# Connectors_2.net
KiCad netlist of a schematic drawn in Altium Designer
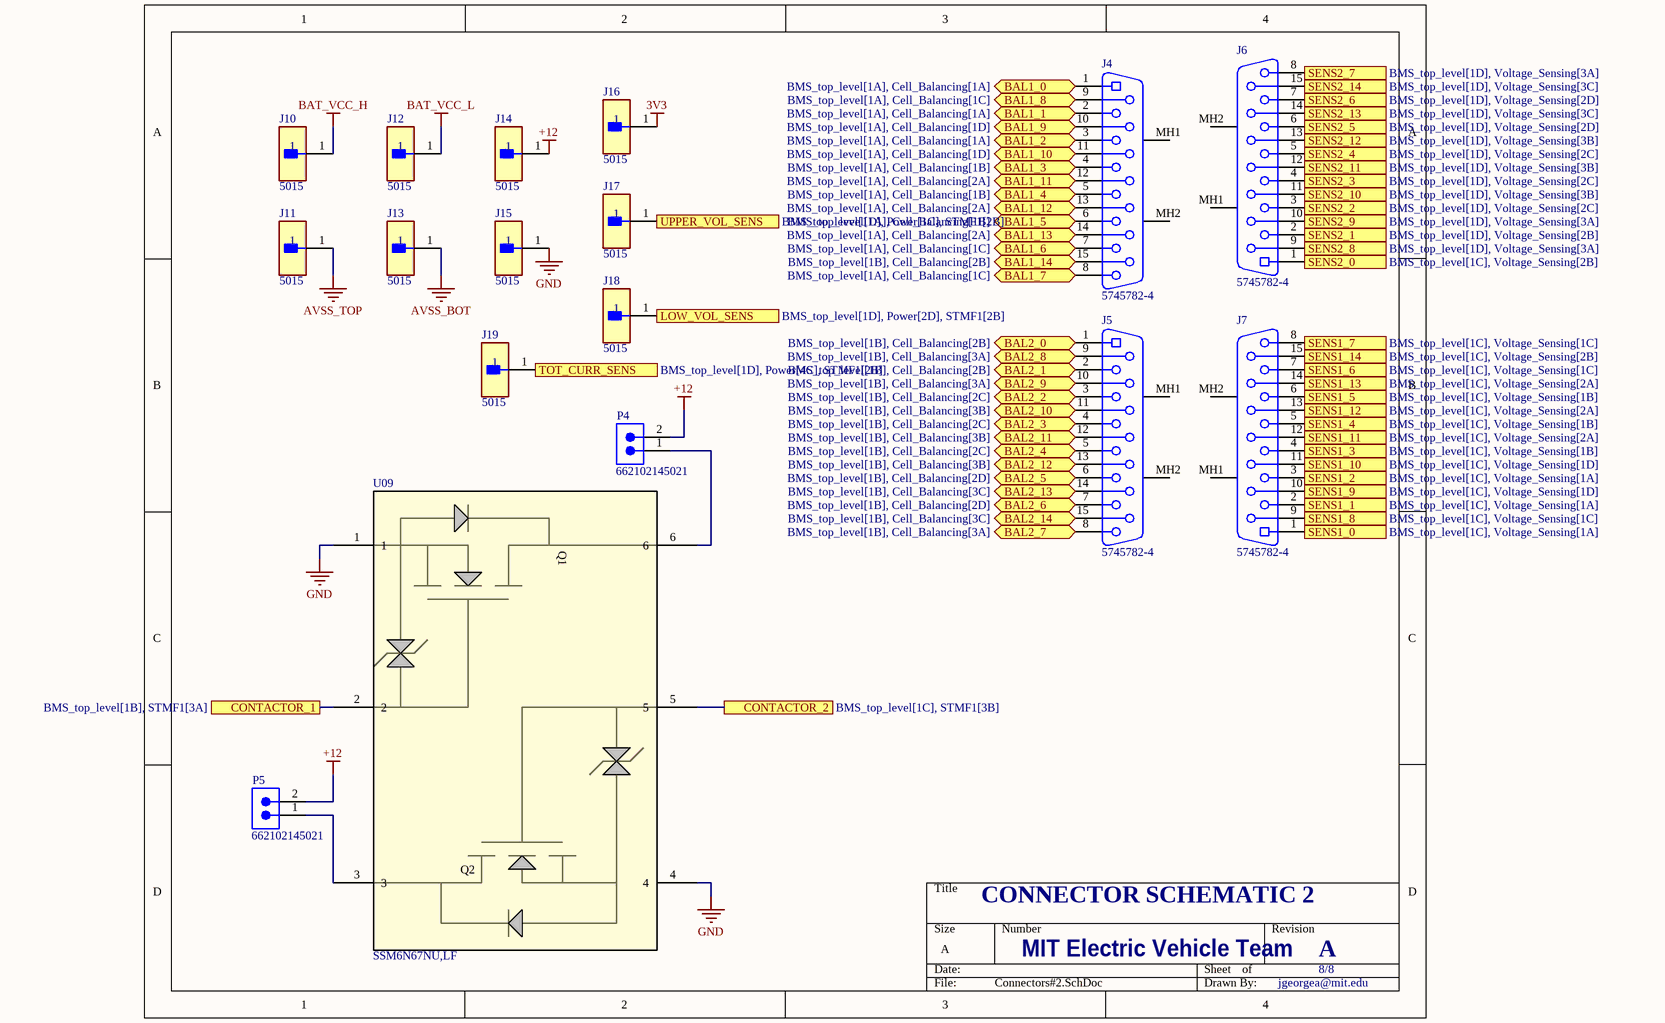
[diagram p0: Connectors#2.SchDoc]

(export (version "E")
  (design (tool "Eeschema 10.0.6"))
  (components
    (comp (ref "J4")
      (value "5745782-4")
      (footprint "TECO-5745782-4_V")
      (fields (field (name "MANUFACTURER") "TE Connectivity"))
      (libsource (lib "") (part "CN-2S-2F-D15_1"))
    )
    (comp (ref "J5")
      (value "5745782-4")
      (footprint "TECO-5745782-4_V")
      (fields (field (name "MANUFACTURER") "TE Connectivity"))
      (libsource (lib "") (part "CN-2S-2F-D15_1"))
    )
    (comp (ref "J6")
      (value "5745782-4")
      (footprint "TECO-5745782-4_V")
      (fields (field (name "MANUFACTURER") "TE Connectivity"))
      (libsource (lib "Altium Content Vault") (part "CN-2S-2F-D15"))
    )
    (comp (ref "J7")
      (value "5745782-4")
      (footprint "TECO-5745782-4_V")
      (fields (field (name "MANUFACTURER") "TE Connectivity"))
      (libsource (lib "Altium Content Vault") (part "CN-2S-2F-D15"))
    )
    (comp (ref "J10")
      (value "5015")
      (footprint "FP-5015-MFG")
      (description "PC TEST POINT MINIATURE")
      (fields
        (field (name "MANUFACTURER") "keystone")
        (field (name "OCTOPART") "https://octopart.com/5015-keystone-3822")
      )
      (libsource (lib "Altium Content Vault") (part "dd45045ce8184df9e99e12baf3f412c"))
    )
    (comp (ref "J11")
      (value "5015")
      (footprint "FP-5015-MFG")
      (description "PC TEST POINT MINIATURE")
      (fields
        (field (name "MANUFACTURER") "keystone")
        (field (name "OCTOPART") "https://octopart.com/5015-keystone-3822")
      )
      (libsource (lib "Altium Content Vault") (part "dd45045ce8184df9e99e12baf3f412c"))
    )
    (comp (ref "J12")
      (value "5015")
      (footprint "FP-5015-MFG")
      (description "PC TEST POINT MINIATURE")
      (fields
        (field (name "MANUFACTURER") "keystone")
        (field (name "OCTOPART") "https://octopart.com/5015-keystone-3822")
      )
      (libsource (lib "Altium Content Vault") (part "dd45045ce8184df9e99e12baf3f412c"))
    )
    (comp (ref "J13")
      (value "5015")
      (footprint "FP-5015-MFG")
      (description "PC TEST POINT MINIATURE")
      (fields
        (field (name "MANUFACTURER") "keystone")
        (field (name "OCTOPART") "https://octopart.com/5015-keystone-3822")
      )
      (libsource (lib "Altium Content Vault") (part "dd45045ce8184df9e99e12baf3f412c"))
    )
    (comp (ref "J14")
      (value "5015")
      (footprint "FP-5015-MFG")
      (description "PC TEST POINT MINIATURE")
      (fields
        (field (name "MANUFACTURER") "keystone")
        (field (name "OCTOPART") "https://octopart.com/5015-keystone-3822")
      )
      (libsource (lib "Altium Content Vault") (part "dd45045ce8184df9e99e12baf3f412c"))
    )
    (comp (ref "J15")
      (value "5015")
      (footprint "FP-5015-MFG")
      (description "PC TEST POINT MINIATURE")
      (fields
        (field (name "MANUFACTURER") "keystone")
        (field (name "OCTOPART") "https://octopart.com/5015-keystone-3822")
      )
      (libsource (lib "Altium Content Vault") (part "dd45045ce8184df9e99e12baf3f412c"))
    )
    (comp (ref "J16")
      (value "5015")
      (footprint "FP-5015-MFG")
      (description "PC TEST POINT MINIATURE")
      (fields
        (field (name "MANUFACTURER") "keystone")
        (field (name "OCTOPART") "https://octopart.com/5015-keystone-3822")
      )
      (libsource (lib "Altium Content Vault") (part "dd45045ce8184df9e99e12baf3f412c"))
    )
    (comp (ref "J17")
      (value "5015")
      (footprint "FP-5015-MFG")
      (description "PC TEST POINT MINIATURE")
      (fields
        (field (name "MANUFACTURER") "keystone")
        (field (name "OCTOPART") "https://octopart.com/5015-keystone-3822")
      )
      (libsource (lib "Altium Content Vault") (part "dd45045ce8184df9e99e12baf3f412c"))
    )
    (comp (ref "J18")
      (value "5015")
      (footprint "FP-5015-MFG")
      (description "PC TEST POINT MINIATURE")
      (fields
        (field (name "MANUFACTURER") "keystone")
        (field (name "OCTOPART") "https://octopart.com/5015-keystone-3822")
      )
      (libsource (lib "Altium Content Vault") (part "dd45045ce8184df9e99e12baf3f412c"))
    )
    (comp (ref "J19")
      (value "5015")
      (footprint "FP-5015-MFG")
      (description "PC TEST POINT MINIATURE")
      (fields
        (field (name "MANUFACTURER") "keystone")
        (field (name "OCTOPART") "https://octopart.com/5015-keystone-3822")
      )
      (libsource (lib "Altium Content Vault") (part "dd45045ce8184df9e99e12baf3f412c"))
    )
    (comp (ref "P4")
      (value "662102145021")
      (footprint "662102145021")
      (libsource (lib "Altium Content Vault") (part "Header_Male_1R_02P"))
    )
    (comp (ref "P5")
      (value "662102145021")
      (footprint "662102145021")
      (libsource (lib "Altium Content Vault") (part "Header_Male_1R_02P"))
    )
    (comp (ref "U09")
      (value "SSM6N67NU,LF")
      (footprint "UDFN6_TOS")
      (description "No Description Available")
      (libsource (lib "SSM6N67NU,LF") (part "SSM6N67NU,LF"))
    )
  )
  (nets
    (net (code "1") (name "+12") (class "Default")
      (node (ref "J14") (pin "1") (pinfunction "1_1") (pintype "passive"))
      (node (ref "P4") (pin "2") (pinfunction "2_2") (pintype "passive"))
      (node (ref "P5") (pin "2") (pinfunction "2_2") (pintype "passive"))
    )
    (net (code "2") (name "/BAL1_0") (class "Default")
      (node (ref "J4") (pin "1") (pinfunction "1_1") (pintype "passive"))
    )
    (net (code "3") (name "/BAL1_1") (class "Default")
      (node (ref "J4") (pin "2") (pinfunction "2_2") (pintype "passive"))
    )
    (net (code "4") (name "/BAL1_2") (class "Default")
      (node (ref "J4") (pin "3") (pinfunction "3_3") (pintype "passive"))
    )
    (net (code "5") (name "/BAL1_3") (class "Default")
      (node (ref "J4") (pin "4") (pinfunction "4_4") (pintype "passive"))
    )
    (net (code "6") (name "/BAL1_4") (class "Default")
      (node (ref "J4") (pin "5") (pinfunction "5_5") (pintype "passive"))
    )
    (net (code "7") (name "/BAL1_5") (class "Default")
      (node (ref "J4") (pin "6") (pinfunction "6_6") (pintype "passive"))
    )
    (net (code "8") (name "/BAL1_6") (class "Default")
      (node (ref "J4") (pin "7") (pinfunction "7_7") (pintype "passive"))
    )
    (net (code "9") (name "/BAL1_7") (class "Default")
      (node (ref "J4") (pin "8") (pinfunction "8_8") (pintype "passive"))
    )
    (net (code "10") (name "/BAL1_8") (class "Default")
      (node (ref "J4") (pin "9") (pinfunction "9_9") (pintype "passive"))
    )
    (net (code "11") (name "/BAL1_9") (class "Default")
      (node (ref "J4") (pin "10") (pinfunction "10_10") (pintype "passive"))
    )
    (net (code "12") (name "/BAL1_10") (class "Default")
      (node (ref "J4") (pin "11") (pinfunction "11_11") (pintype "passive"))
    )
    (net (code "13") (name "/BAL1_11") (class "Default")
      (node (ref "J4") (pin "12") (pinfunction "12_12") (pintype "passive"))
    )
    (net (code "14") (name "/BAL1_12") (class "Default")
      (node (ref "J4") (pin "13") (pinfunction "13_13") (pintype "passive"))
    )
    (net (code "15") (name "/BAL1_13") (class "Default")
      (node (ref "J4") (pin "14") (pinfunction "14_14") (pintype "passive"))
    )
    (net (code "16") (name "/BAL1_14") (class "Default")
      (node (ref "J4") (pin "15") (pinfunction "15_15") (pintype "passive"))
    )
    (net (code "17") (name "/BAL2_0") (class "Default")
      (node (ref "J5") (pin "1") (pinfunction "1_1") (pintype "passive"))
    )
    (net (code "18") (name "/BAL2_1") (class "Default")
      (node (ref "J5") (pin "2") (pinfunction "2_2") (pintype "passive"))
    )
    (net (code "19") (name "/BAL2_2") (class "Default")
      (node (ref "J5") (pin "3") (pinfunction "3_3") (pintype "passive"))
    )
    (net (code "20") (name "/BAL2_3") (class "Default")
      (node (ref "J5") (pin "4") (pinfunction "4_4") (pintype "passive"))
    )
    (net (code "21") (name "/BAL2_4") (class "Default")
      (node (ref "J5") (pin "5") (pinfunction "5_5") (pintype "passive"))
    )
    (net (code "22") (name "/BAL2_5") (class "Default")
      (node (ref "J5") (pin "6") (pinfunction "6_6") (pintype "passive"))
    )
    (net (code "23") (name "/BAL2_6") (class "Default")
      (node (ref "J5") (pin "7") (pinfunction "7_7") (pintype "passive"))
    )
    (net (code "24") (name "/BAL2_7") (class "Default")
      (node (ref "J5") (pin "8") (pinfunction "8_8") (pintype "passive"))
    )
    (net (code "25") (name "/BAL2_8") (class "Default")
      (node (ref "J5") (pin "9") (pinfunction "9_9") (pintype "passive"))
    )
    (net (code "26") (name "/BAL2_9") (class "Default")
      (node (ref "J5") (pin "10") (pinfunction "10_10") (pintype "passive"))
    )
    (net (code "27") (name "/BAL2_10") (class "Default")
      (node (ref "J5") (pin "11") (pinfunction "11_11") (pintype "passive"))
    )
    (net (code "28") (name "/BAL2_11") (class "Default")
      (node (ref "J5") (pin "12") (pinfunction "12_12") (pintype "passive"))
    )
    (net (code "29") (name "/BAL2_12") (class "Default")
      (node (ref "J5") (pin "13") (pinfunction "13_13") (pintype "passive"))
    )
    (net (code "30") (name "/BAL2_13") (class "Default")
      (node (ref "J5") (pin "14") (pinfunction "14_14") (pintype "passive"))
    )
    (net (code "31") (name "/BAL2_14") (class "Default")
      (node (ref "J5") (pin "15") (pinfunction "15_15") (pintype "passive"))
    )
    (net (code "32") (name "/CONTACTOR_1") (class "Default")
      (node (ref "U09") (pin "2") (pinfunction "2_2") (pintype "passive"))
    )
    (net (code "33") (name "/CONTACTOR_2") (class "Default")
      (node (ref "U09") (pin "5") (pinfunction "5_5") (pintype "passive"))
    )
    (net (code "34") (name "/LOW_VOL_SENS") (class "Default")
      (node (ref "J18") (pin "1") (pinfunction "1_1") (pintype "passive"))
    )
    (net (code "35") (name "/SENS1_0") (class "Default")
      (node (ref "J7") (pin "1") (pinfunction "1_1") (pintype "passive"))
    )
    (net (code "36") (name "/SENS1_1") (class "Default")
      (node (ref "J7") (pin "2") (pinfunction "2_2") (pintype "passive"))
    )
    (net (code "37") (name "/SENS1_2") (class "Default")
      (node (ref "J7") (pin "3") (pinfunction "3_3") (pintype "passive"))
    )
    (net (code "38") (name "/SENS1_3") (class "Default")
      (node (ref "J7") (pin "4") (pinfunction "4_4") (pintype "passive"))
    )
    (net (code "39") (name "/SENS1_4") (class "Default")
      (node (ref "J7") (pin "5") (pinfunction "5_5") (pintype "passive"))
    )
    (net (code "40") (name "/SENS1_5") (class "Default")
      (node (ref "J7") (pin "6") (pinfunction "6_6") (pintype "passive"))
    )
    (net (code "41") (name "/SENS1_6") (class "Default")
      (node (ref "J7") (pin "7") (pinfunction "7_7") (pintype "passive"))
    )
    (net (code "42") (name "/SENS1_7") (class "Default")
      (node (ref "J7") (pin "8") (pinfunction "8_8") (pintype "passive"))
    )
    (net (code "43") (name "/SENS1_8") (class "Default")
      (node (ref "J7") (pin "9") (pinfunction "9_9") (pintype "passive"))
    )
    (net (code "44") (name "/SENS1_9") (class "Default")
      (node (ref "J7") (pin "10") (pinfunction "10_10") (pintype "passive"))
    )
    (net (code "45") (name "/SENS1_10") (class "Default")
      (node (ref "J7") (pin "11") (pinfunction "11_11") (pintype "passive"))
    )
    (net (code "46") (name "/SENS1_11") (class "Default")
      (node (ref "J7") (pin "12") (pinfunction "12_12") (pintype "passive"))
    )
    (net (code "47") (name "/SENS1_12") (class "Default")
      (node (ref "J7") (pin "13") (pinfunction "13_13") (pintype "passive"))
    )
    (net (code "48") (name "/SENS1_13") (class "Default")
      (node (ref "J7") (pin "14") (pinfunction "14_14") (pintype "passive"))
    )
    (net (code "49") (name "/SENS1_14") (class "Default")
      (node (ref "J7") (pin "15") (pinfunction "15_15") (pintype "passive"))
    )
    (net (code "50") (name "/SENS2_0") (class "Default")
      (node (ref "J6") (pin "1") (pinfunction "1_1") (pintype "passive"))
    )
    (net (code "51") (name "/SENS2_1") (class "Default")
      (node (ref "J6") (pin "2") (pinfunction "2_2") (pintype "passive"))
    )
    (net (code "52") (name "/SENS2_2") (class "Default")
      (node (ref "J6") (pin "3") (pinfunction "3_3") (pintype "passive"))
    )
    (net (code "53") (name "/SENS2_3") (class "Default")
      (node (ref "J6") (pin "4") (pinfunction "4_4") (pintype "passive"))
    )
    (net (code "54") (name "/SENS2_4") (class "Default")
      (node (ref "J6") (pin "5") (pinfunction "5_5") (pintype "passive"))
    )
    (net (code "55") (name "/SENS2_5") (class "Default")
      (node (ref "J6") (pin "6") (pinfunction "6_6") (pintype "passive"))
    )
    (net (code "56") (name "/SENS2_6") (class "Default")
      (node (ref "J6") (pin "7") (pinfunction "7_7") (pintype "passive"))
    )
    (net (code "57") (name "/SENS2_7") (class "Default")
      (node (ref "J6") (pin "8") (pinfunction "8_8") (pintype "passive"))
    )
    (net (code "58") (name "/SENS2_8") (class "Default")
      (node (ref "J6") (pin "9") (pinfunction "9_9") (pintype "passive"))
    )
    (net (code "59") (name "/SENS2_9") (class "Default")
      (node (ref "J6") (pin "10") (pinfunction "10_10") (pintype "passive"))
    )
    (net (code "60") (name "/SENS2_10") (class "Default")
      (node (ref "J6") (pin "11") (pinfunction "11_11") (pintype "passive"))
    )
    (net (code "61") (name "/SENS2_11") (class "Default")
      (node (ref "J6") (pin "12") (pinfunction "12_12") (pintype "passive"))
    )
    (net (code "62") (name "/SENS2_12") (class "Default")
      (node (ref "J6") (pin "13") (pinfunction "13_13") (pintype "passive"))
    )
    (net (code "63") (name "/SENS2_13") (class "Default")
      (node (ref "J6") (pin "14") (pinfunction "14_14") (pintype "passive"))
    )
    (net (code "64") (name "/SENS2_14") (class "Default")
      (node (ref "J6") (pin "15") (pinfunction "15_15") (pintype "passive"))
    )
    (net (code "65") (name "/TOT_CURR_SENS") (class "Default")
      (node (ref "J19") (pin "1") (pinfunction "1_1") (pintype "passive"))
    )
    (net (code "66") (name "/UPPER_VOL_SENS") (class "Default")
      (node (ref "J17") (pin "1") (pinfunction "1_1") (pintype "passive"))
    )
    (net (code "67") (name "3V3") (class "Default")
      (node (ref "J16") (pin "1") (pinfunction "1_1") (pintype "passive"))
    )
    (net (code "68") (name "AVSS_BOT") (class "Default")
      (node (ref "J13") (pin "1") (pinfunction "1_1") (pintype "passive"))
    )
    (net (code "69") (name "AVSS_TOP") (class "Default")
      (node (ref "J11") (pin "1") (pinfunction "1_1") (pintype "passive"))
    )
    (net (code "70") (name "BAT_VCC_H") (class "Default")
      (node (ref "J10") (pin "1") (pinfunction "1_1") (pintype "passive"))
    )
    (net (code "71") (name "BAT_VCC_L") (class "Default")
      (node (ref "J12") (pin "1") (pinfunction "1_1") (pintype "passive"))
    )
    (net (code "72") (name "GND") (class "Default")
      (node (ref "J15") (pin "1") (pinfunction "1_1") (pintype "passive"))
      (node (ref "U09") (pin "1") (pinfunction "1_1") (pintype "passive"))
      (node (ref "U09") (pin "4") (pinfunction "4_4") (pintype "passive"))
    )
    (net (code "73") (name "Net-(P4-Pad1)") (class "Default")
      (node (ref "P4") (pin "1") (pinfunction "1_1") (pintype "passive"))
      (node (ref "U09") (pin "6") (pinfunction "6_6") (pintype "passive"))
    )
    (net (code "74") (name "Net-(P5-Pad1)") (class "Default")
      (node (ref "P5") (pin "1") (pinfunction "1_1") (pintype "passive"))
      (node (ref "U09") (pin "3") (pinfunction "3_3") (pintype "passive"))
    )
    (net (code "75") (name "unconnected-(J4-PadMH1)") (class "Default")
      (node (ref "J4") (pin "MH1") (pinfunction "MH1_MH1") (pintype "passive"))
    )
    (net (code "76") (name "unconnected-(J4-PadMH2)") (class "Default")
      (node (ref "J4") (pin "MH2") (pinfunction "MH2_MH2") (pintype "passive"))
    )
    (net (code "77") (name "unconnected-(J5-PadMH1)") (class "Default")
      (node (ref "J5") (pin "MH1") (pinfunction "MH1_MH1") (pintype "passive"))
    )
    (net (code "78") (name "unconnected-(J5-PadMH2)") (class "Default")
      (node (ref "J5") (pin "MH2") (pinfunction "MH2_MH2") (pintype "passive"))
    )
    (net (code "79") (name "unconnected-(J6-PadMH1)") (class "Default")
      (node (ref "J6") (pin "MH1") (pinfunction "MH1_MH1") (pintype "passive"))
    )
    (net (code "80") (name "unconnected-(J6-PadMH2)") (class "Default")
      (node (ref "J6") (pin "MH2") (pinfunction "MH2_MH2") (pintype "passive"))
    )
    (net (code "81") (name "unconnected-(J7-PadMH1)") (class "Default")
      (node (ref "J7") (pin "MH1") (pinfunction "MH1_MH1") (pintype "passive"))
    )
    (net (code "82") (name "unconnected-(J7-PadMH2)") (class "Default")
      (node (ref "J7") (pin "MH2") (pinfunction "MH2_MH2") (pintype "passive"))
    )
  )
)
